# Processor.net
KiCad netlist of a schematic drawn in EAGLE
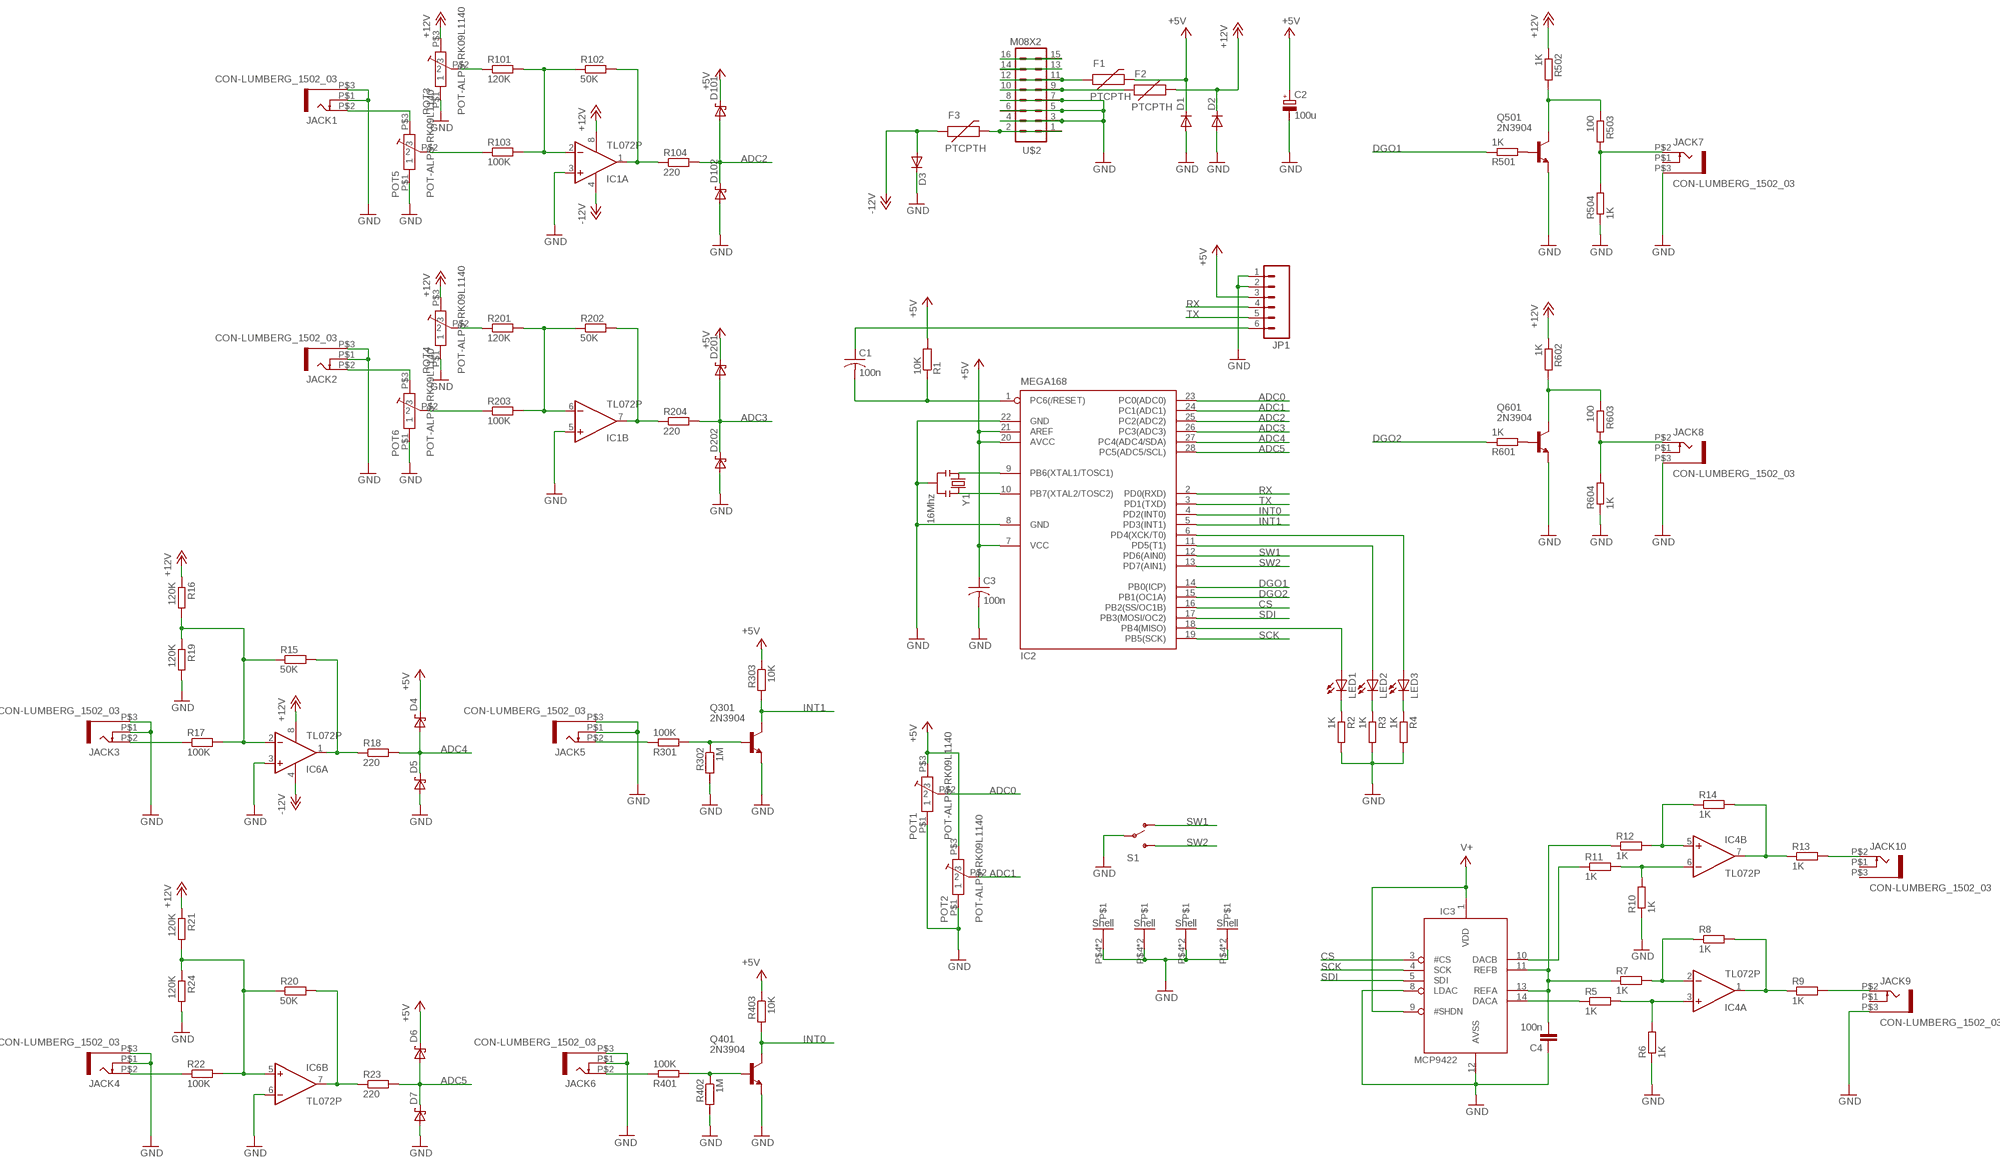
[diagram p0: schematic, sheet 1]

(export (version "E")
  (design (tool "Eeschema 10.0.6"))
  (components
    (comp (ref "C1")
      (value "100n")
      (footprint "eagle-import:C050-024X044")
      (libsource (lib "eagle-import") (part "C-US050-024X044"))
    )
    (comp (ref "C2")
      (value "100u")
      (footprint "eagle-import:E5-6")
      (libsource (lib "eagle-import") (part "CPOL-EUE5-6"))
    )
    (comp (ref "C3")
      (value "100n")
      (footprint "eagle-import:C050-024X044")
      (libsource (lib "eagle-import") (part "C-US050-024X044"))
    )
    (comp (ref "C4")
      (value "100n")
      (footprint "eagle-import:C050-030X075")
      (libsource (lib "eagle-import") (part "C-EU050-030X075"))
    )
    (comp (ref "D1")
      (value "DIODEPTH")
      (footprint "eagle-import:DIODE-1N4001")
      (libsource (lib "eagle-import") (part "DIODEPTH"))
    )
    (comp (ref "D2")
      (value "DIODEPTH")
      (footprint "eagle-import:DIODE-1N4001")
      (libsource (lib "eagle-import") (part "DIODEPTH"))
    )
    (comp (ref "D3")
      (value "DIODEPTH")
      (footprint "eagle-import:DIODE-1N4001")
      (libsource (lib "eagle-import") (part "DIODEPTH"))
    )
    (comp (ref "D4")
      (value "DS_E2L")
      (footprint "eagle-import:E2LINE")
      (libsource (lib "eagle-import") (part "DS_E2L"))
    )
    (comp (ref "D5")
      (value "DS_E2L")
      (footprint "eagle-import:E2LINE")
      (fields (field (name "OC_FARNELL") "unknown") (field (name "OC_NEWARK") "unknown"))
      (libsource (lib "eagle-import") (part "DS_E2L"))
    )
    (comp (ref "D6")
      (value "DS_E2L")
      (footprint "eagle-import:E2LINE")
      (libsource (lib "eagle-import") (part "DS_E2L"))
    )
    (comp (ref "D7")
      (value "DS_E2L")
      (footprint "eagle-import:E2LINE")
      (fields (field (name "OC_FARNELL") "unknown") (field (name "OC_NEWARK") "unknown"))
      (libsource (lib "eagle-import") (part "DS_E2L"))
    )
    (comp (ref "D101")
      (value "DS_E2L")
      (footprint "eagle-import:E2LINE")
      (libsource (lib "eagle-import") (part "DS_E2L"))
    )
    (comp (ref "D102")
      (value "DS_E2L")
      (footprint "eagle-import:E2LINE")
      (fields (field (name "OC_FARNELL") "unknown") (field (name "OC_NEWARK") "unknown"))
      (libsource (lib "eagle-import") (part "DS_E2L"))
    )
    (comp (ref "D201")
      (value "DS_E2L")
      (footprint "eagle-import:E2LINE")
      (libsource (lib "eagle-import") (part "DS_E2L"))
    )
    (comp (ref "D202")
      (value "DS_E2L")
      (footprint "eagle-import:E2LINE")
      (fields (field (name "OC_FARNELL") "unknown") (field (name "OC_NEWARK") "unknown"))
      (libsource (lib "eagle-import") (part "DS_E2L"))
    )
    (comp (ref "F1")
      (value "PTCPTH")
      (footprint "eagle-import:PTC")
      (libsource (lib "eagle-import") (part "PTCPTH"))
    )
    (comp (ref "F2")
      (value "PTCPTH")
      (footprint "eagle-import:PTC")
      (libsource (lib "eagle-import") (part "PTCPTH"))
    )
    (comp (ref "F3")
      (value "PTCPTH")
      (footprint "eagle-import:PTC")
      (libsource (lib "eagle-import") (part "PTCPTH"))
    )
    (comp (ref "IC1")
      (value "TL072P")
      (footprint "eagle-import:DIL08")
      (libsource (lib "eagle-import") (part "TL072P"))
    )
    (comp (ref "IC2")
      (value "MEGA168")
      (footprint "eagle-import:DIL28-3")
      (libsource (lib "eagle-import") (part "MEGA8-P"))
    )
    (comp (ref "IC3")
      (value "MCP9422")
      (footprint "eagle-import:DIL14")
      (libsource (lib "eagle-import") (part "MCP9422"))
    )
    (comp (ref "IC4")
      (value "TL072P")
      (footprint "eagle-import:DIL08")
      (libsource (lib "eagle-import") (part "TL072P"))
    )
    (comp (ref "IC6")
      (value "TL072P")
      (footprint "eagle-import:DIL08")
      (libsource (lib "eagle-import") (part "TL072P"))
    )
    (comp (ref "JACK1")
      (value "CON-LUMBERG_1502_03")
      (footprint "eagle-import:CON-LUMBERG_1502_03")
      (libsource (lib "eagle-import") (part "CON-LUMBERG_1502_03"))
    )
    (comp (ref "JACK2")
      (value "CON-LUMBERG_1502_03")
      (footprint "eagle-import:CON-LUMBERG_1502_03")
      (libsource (lib "eagle-import") (part "CON-LUMBERG_1502_03"))
    )
    (comp (ref "JACK3")
      (value "CON-LUMBERG_1502_03")
      (footprint "eagle-import:CON-LUMBERG_1502_03")
      (libsource (lib "eagle-import") (part "CON-LUMBERG_1502_03"))
    )
    (comp (ref "JACK4")
      (value "CON-LUMBERG_1502_03")
      (footprint "eagle-import:CON-LUMBERG_1502_03")
      (libsource (lib "eagle-import") (part "CON-LUMBERG_1502_03"))
    )
    (comp (ref "JACK5")
      (value "CON-LUMBERG_1502_03")
      (footprint "eagle-import:CON-LUMBERG_1502_03")
      (libsource (lib "eagle-import") (part "CON-LUMBERG_1502_03"))
    )
    (comp (ref "JACK6")
      (value "CON-LUMBERG_1502_03")
      (footprint "eagle-import:CON-LUMBERG_1502_03")
      (libsource (lib "eagle-import") (part "CON-LUMBERG_1502_03"))
    )
    (comp (ref "JACK7")
      (value "CON-LUMBERG_1502_03")
      (footprint "eagle-import:CON-LUMBERG_1502_03")
      (libsource (lib "eagle-import") (part "CON-LUMBERG_1502_03"))
    )
    (comp (ref "JACK8")
      (value "CON-LUMBERG_1502_03")
      (footprint "eagle-import:CON-LUMBERG_1502_03")
      (libsource (lib "eagle-import") (part "CON-LUMBERG_1502_03"))
    )
    (comp (ref "JACK9")
      (value "CON-LUMBERG_1502_03")
      (footprint "eagle-import:CON-LUMBERG_1502_03")
      (libsource (lib "eagle-import") (part "CON-LUMBERG_1502_03"))
    )
    (comp (ref "JACK10")
      (value "CON-LUMBERG_1502_03")
      (footprint "eagle-import:CON-LUMBERG_1502_03")
      (libsource (lib "eagle-import") (part "CON-LUMBERG_1502_03"))
    )
    (comp (ref "JP1")
      (value "M06SIP")
      (footprint "eagle-import:1X06")
      (libsource (lib "eagle-import") (part "M06SIP"))
    )
    (comp (ref "LED1")
      (value "LED3MM")
      (footprint "eagle-import:LED3MM")
      (libsource (lib "eagle-import") (part "LED3MM"))
    )
    (comp (ref "LED2")
      (value "LED3MM")
      (footprint "eagle-import:LED3MM")
      (libsource (lib "eagle-import") (part "LED3MM"))
    )
    (comp (ref "LED3")
      (value "LED3MM")
      (footprint "eagle-import:LED3MM")
      (libsource (lib "eagle-import") (part "LED3MM"))
    )
    (comp (ref "POT1")
      (value "POT-ALPS-RK09L1140")
      (footprint "eagle-import:POT-ALPS-RK09L1140")
      (libsource (lib "eagle-import") (part "POT-ALPS-RK09L1140"))
    )
    (comp (ref "POT2")
      (value "POT-ALPS-RK09L1140")
      (footprint "eagle-import:POT-ALPS-RK09L1140")
      (libsource (lib "eagle-import") (part "POT-ALPS-RK09L1140"))
    )
    (comp (ref "POT3")
      (value "POT-ALPS-RK09L1140")
      (footprint "eagle-import:POT-ALPS-RK09L1140")
      (libsource (lib "eagle-import") (part "POT-ALPS-RK09L1140"))
    )
    (comp (ref "POT4")
      (value "POT-ALPS-RK09L1140")
      (footprint "eagle-import:POT-ALPS-RK09L1140")
      (libsource (lib "eagle-import") (part "POT-ALPS-RK09L1140"))
    )
    (comp (ref "POT5")
      (value "POT-ALPS-RK09L1140")
      (footprint "eagle-import:POT-ALPS-RK09L1140")
      (libsource (lib "eagle-import") (part "POT-ALPS-RK09L1140"))
    )
    (comp (ref "POT6")
      (value "POT-ALPS-RK09L1140")
      (footprint "eagle-import:POT-ALPS-RK09L1140")
      (libsource (lib "eagle-import") (part "POT-ALPS-RK09L1140"))
    )
    (comp (ref "Q301")
      (value "2N3904")
      (footprint "eagle-import:TO92")
      (libsource (lib "eagle-import") (part "2N3904"))
    )
    (comp (ref "Q401")
      (value "2N3904")
      (footprint "eagle-import:TO92")
      (libsource (lib "eagle-import") (part "2N3904"))
    )
    (comp (ref "Q501")
      (value "2N3904")
      (footprint "eagle-import:TO92")
      (libsource (lib "eagle-import") (part "2N3904"))
    )
    (comp (ref "Q601")
      (value "2N3904")
      (footprint "eagle-import:TO92")
      (libsource (lib "eagle-import") (part "2N3904"))
    )
    (comp (ref "R1")
      (value "10K")
      (footprint "eagle-import:0204_7")
      (libsource (lib "eagle-import") (part "R-EU_0204/7"))
    )
    (comp (ref "R2")
      (value "1K")
      (footprint "eagle-import:0204_7")
      (libsource (lib "eagle-import") (part "R-EU_0204/7"))
    )
    (comp (ref "R3")
      (value "1K")
      (footprint "eagle-import:0204_7")
      (libsource (lib "eagle-import") (part "R-EU_0204/7"))
    )
    (comp (ref "R4")
      (value "1K")
      (footprint "eagle-import:0204_7")
      (libsource (lib "eagle-import") (part "R-EU_0204/7"))
    )
    (comp (ref "R5")
      (value "1K")
      (footprint "eagle-import:0204_7")
      (libsource (lib "eagle-import") (part "R-EU_0204/7"))
    )
    (comp (ref "R6")
      (value "1K")
      (footprint "eagle-import:0204_7")
      (libsource (lib "eagle-import") (part "R-EU_0204/7"))
    )
    (comp (ref "R7")
      (value "1K")
      (footprint "eagle-import:0204_7")
      (libsource (lib "eagle-import") (part "R-EU_0204/7"))
    )
    (comp (ref "R8")
      (value "1K")
      (footprint "eagle-import:0204_7")
      (libsource (lib "eagle-import") (part "R-EU_0204/7"))
    )
    (comp (ref "R9")
      (value "1K")
      (footprint "eagle-import:0204_7")
      (libsource (lib "eagle-import") (part "R-EU_0204/7"))
    )
    (comp (ref "R10")
      (value "1K")
      (footprint "eagle-import:0204_7")
      (libsource (lib "eagle-import") (part "R-EU_0204/7"))
    )
    (comp (ref "R11")
      (value "1K")
      (footprint "eagle-import:0204_7")
      (libsource (lib "eagle-import") (part "R-EU_0204/7"))
    )
    (comp (ref "R12")
      (value "1K")
      (footprint "eagle-import:0204_7")
      (libsource (lib "eagle-import") (part "R-EU_0204/7"))
    )
    (comp (ref "R13")
      (value "1K")
      (footprint "eagle-import:0204_7")
      (libsource (lib "eagle-import") (part "R-EU_0204/7"))
    )
    (comp (ref "R14")
      (value "1K")
      (footprint "eagle-import:0204_7")
      (libsource (lib "eagle-import") (part "R-EU_0204/7"))
    )
    (comp (ref "R15")
      (value "50K")
      (footprint "eagle-import:0204_7")
      (libsource (lib "eagle-import") (part "resistor_R-EU_0204/7"))
    )
    (comp (ref "R16")
      (value "120K")
      (footprint "eagle-import:0204_7")
      (libsource (lib "eagle-import") (part "resistor_R-EU_0204/7"))
    )
    (comp (ref "R17")
      (value "100K")
      (footprint "eagle-import:0204_7")
      (libsource (lib "eagle-import") (part "resistor_R-EU_0204/7"))
    )
    (comp (ref "R18")
      (value "220")
      (footprint "eagle-import:0204_7")
      (libsource (lib "eagle-import") (part "resistor_R-EU_0204/7"))
    )
    (comp (ref "R19")
      (value "120K")
      (footprint "eagle-import:0204_7")
      (libsource (lib "eagle-import") (part "resistor_R-EU_0204/7"))
    )
    (comp (ref "R20")
      (value "50K")
      (footprint "eagle-import:0204_7")
      (libsource (lib "eagle-import") (part "resistor_R-EU_0204/7"))
    )
    (comp (ref "R21")
      (value "120K")
      (footprint "eagle-import:0204_7")
      (libsource (lib "eagle-import") (part "resistor_R-EU_0204/7"))
    )
    (comp (ref "R22")
      (value "100K")
      (footprint "eagle-import:0204_7")
      (libsource (lib "eagle-import") (part "resistor_R-EU_0204/7"))
    )
    (comp (ref "R23")
      (value "220")
      (footprint "eagle-import:0204_7")
      (libsource (lib "eagle-import") (part "resistor_R-EU_0204/7"))
    )
    (comp (ref "R24")
      (value "120K")
      (footprint "eagle-import:0204_7")
      (libsource (lib "eagle-import") (part "resistor_R-EU_0204/7"))
    )
    (comp (ref "R101")
      (value "120K")
      (footprint "eagle-import:0204_7")
      (libsource (lib "eagle-import") (part "resistor_R-EU_0204/7"))
    )
    (comp (ref "R102")
      (value "50K")
      (footprint "eagle-import:0204_7")
      (libsource (lib "eagle-import") (part "resistor_R-EU_0204/7"))
    )
    (comp (ref "R103")
      (value "100K")
      (footprint "eagle-import:0204_7")
      (libsource (lib "eagle-import") (part "resistor_R-EU_0204/7"))
    )
    (comp (ref "R104")
      (value "220")
      (footprint "eagle-import:0204_7")
      (libsource (lib "eagle-import") (part "resistor_R-EU_0204/7"))
    )
    (comp (ref "R201")
      (value "120K")
      (footprint "eagle-import:0204_7")
      (libsource (lib "eagle-import") (part "resistor_R-EU_0204/7"))
    )
    (comp (ref "R202")
      (value "50K")
      (footprint "eagle-import:0204_7")
      (libsource (lib "eagle-import") (part "resistor_R-EU_0204/7"))
    )
    (comp (ref "R203")
      (value "100K")
      (footprint "eagle-import:0204_7")
      (libsource (lib "eagle-import") (part "resistor_R-EU_0204/7"))
    )
    (comp (ref "R204")
      (value "220")
      (footprint "eagle-import:0204_7")
      (libsource (lib "eagle-import") (part "resistor_R-EU_0204/7"))
    )
    (comp (ref "R301")
      (value "100K")
      (footprint "eagle-import:0204_7")
      (libsource (lib "eagle-import") (part "R-EU_0204/7"))
    )
    (comp (ref "R302")
      (value "1M")
      (footprint "eagle-import:0204_7")
      (libsource (lib "eagle-import") (part "R-EU_0204/7"))
    )
    (comp (ref "R303")
      (value "10K")
      (footprint "eagle-import:0204_7")
      (libsource (lib "eagle-import") (part "R-EU_0204/7"))
    )
    (comp (ref "R401")
      (value "100K")
      (footprint "eagle-import:0204_7")
      (libsource (lib "eagle-import") (part "R-EU_0204/7"))
    )
    (comp (ref "R402")
      (value "1M")
      (footprint "eagle-import:0204_7")
      (libsource (lib "eagle-import") (part "R-EU_0204/7"))
    )
    (comp (ref "R403")
      (value "10K")
      (footprint "eagle-import:0204_7")
      (libsource (lib "eagle-import") (part "R-EU_0204/7"))
    )
    (comp (ref "R501")
      (value "1K")
      (footprint "eagle-import:0204_7")
      (libsource (lib "eagle-import") (part "R-EU_0204/7"))
    )
    (comp (ref "R502")
      (value "1K")
      (footprint "eagle-import:0204_7")
      (libsource (lib "eagle-import") (part "R-EU_0204/7"))
    )
    (comp (ref "R503")
      (value "100")
      (footprint "eagle-import:0204_7")
      (libsource (lib "eagle-import") (part "R-EU_0204/7"))
    )
    (comp (ref "R504")
      (value "1K")
      (footprint "eagle-import:0204_7")
      (libsource (lib "eagle-import") (part "R-EU_0204/7"))
    )
    (comp (ref "R601")
      (value "1K")
      (footprint "eagle-import:0204_7")
      (libsource (lib "eagle-import") (part "R-EU_0204/7"))
    )
    (comp (ref "R602")
      (value "1K")
      (footprint "eagle-import:0204_7")
      (libsource (lib "eagle-import") (part "R-EU_0204/7"))
    )
    (comp (ref "R603")
      (value "100")
      (footprint "eagle-import:0204_7")
      (libsource (lib "eagle-import") (part "R-EU_0204/7"))
    )
    (comp (ref "R604")
      (value "1K")
      (footprint "eagle-import:0204_7")
      (libsource (lib "eagle-import") (part "R-EU_0204/7"))
    )
    (comp (ref "S1")
      (value "SWITCH-SPST")
      (footprint "eagle-import:SWITCH-SPDT-SALECOM-T8014")
      (libsource (lib "eagle-import") (part "SWITCH-SPST"))
    )
    (comp (ref "U$2")
      (value "M08X2")
      (footprint "eagle-import:2X8")
      (libsource (lib "eagle-import") (part "M08X2"))
    )
    (comp (ref "Y1")
      (value "16Mhz")
      (footprint "eagle-import:RESONATOR-PTH")
      (libsource (lib "eagle-import") (part "RESONATORPTH"))
    )
  )
  (nets
    (net (code "1") (name "+5V") (class "Default")
      (node (ref "C2") (pin "+") (pinfunction "+_+") (pintype "passive"))
      (node (ref "C3") (pin "1") (pinfunction "1_1") (pintype "passive"))
      (node (ref "D1") (pin "C") (pinfunction "C_C") (pintype "passive"))
      (node (ref "D101") (pin "1") (pinfunction "K_1") (pintype "passive"))
      (node (ref "D201") (pin "1") (pinfunction "K_1") (pintype "passive"))
      (node (ref "D4") (pin "1") (pinfunction "K_1") (pintype "passive"))
      (node (ref "D6") (pin "1") (pinfunction "K_1") (pintype "passive"))
      (node (ref "F1") (pin "P$2") (pinfunction "2_P$2") (pintype "bidirectional"))
      (node (ref "IC2") (pin "20") (pinfunction "AVCC_20") (pintype "power_in"))
      (node (ref "IC2") (pin "21") (pinfunction "AREF_21") (pintype "passive"))
      (node (ref "IC2") (pin "7") (pinfunction "VCC_7") (pintype "power_in"))
      (node (ref "JP1") (pin "3") (pinfunction "3_3") (pintype "passive"))
      (node (ref "POT1") (pin "P$3") (pinfunction "3_P$3") (pintype "bidirectional"))
      (node (ref "POT2") (pin "P$3") (pinfunction "3_P$3") (pintype "bidirectional"))
      (node (ref "R1") (pin "2") (pinfunction "2_2") (pintype "passive"))
      (node (ref "R303") (pin "1") (pinfunction "1_1") (pintype "passive"))
      (node (ref "R403") (pin "1") (pinfunction "1_1") (pintype "passive"))
    )
    (net (code "2") (name "+12V") (class "Default")
      (node (ref "D2") (pin "C") (pinfunction "C_C") (pintype "passive"))
      (node (ref "F2") (pin "P$2") (pinfunction "2_P$2") (pintype "bidirectional"))
      (node (ref "IC1") (pin "8") (pinfunction "V+_8") (pintype "power_in"))
      (node (ref "IC6") (pin "8") (pinfunction "V+_8") (pintype "power_in"))
      (node (ref "POT3") (pin "P$3") (pinfunction "3_P$3") (pintype "bidirectional"))
      (node (ref "POT4") (pin "P$3") (pinfunction "3_P$3") (pintype "bidirectional"))
      (node (ref "R16") (pin "1") (pinfunction "1_1") (pintype "passive"))
      (node (ref "R21") (pin "1") (pinfunction "1_1") (pintype "passive"))
      (node (ref "R502") (pin "1") (pinfunction "1_1") (pintype "passive"))
      (node (ref "R602") (pin "1") (pinfunction "1_1") (pintype "passive"))
    )
    (net (code "3") (name "-12V") (class "Default")
      (node (ref "D3") (pin "A") (pinfunction "A_A") (pintype "passive"))
      (node (ref "F3") (pin "P$1") (pinfunction "1_P$1") (pintype "bidirectional"))
      (node (ref "IC1") (pin "4") (pinfunction "V-_4") (pintype "power_in"))
      (node (ref "IC6") (pin "4") (pinfunction "V-_4") (pintype "power_in"))
    )
    (net (code "4") (name "/ADC0") (class "Default")
      (node (ref "IC2") (pin "23") (pinfunction "PC0(ADC0)_23") (pintype "bidirectional"))
      (node (ref "POT1") (pin "P$2") (pinfunction "2_P$2") (pintype "bidirectional"))
    )
    (net (code "5") (name "/ADC1") (class "Default")
      (node (ref "IC2") (pin "24") (pinfunction "PC1(ADC1)_24") (pintype "bidirectional"))
      (node (ref "POT2") (pin "P$2") (pinfunction "2_P$2") (pintype "bidirectional"))
    )
    (net (code "6") (name "/ADC2") (class "Default")
      (node (ref "D101") (pin "2") (pinfunction "A_2") (pintype "passive"))
      (node (ref "D102") (pin "1") (pinfunction "K_1") (pintype "passive"))
      (node (ref "IC2") (pin "25") (pinfunction "PC2(ADC2)_25") (pintype "bidirectional"))
      (node (ref "R104") (pin "2") (pinfunction "2_2") (pintype "passive"))
    )
    (net (code "7") (name "/ADC3") (class "Default")
      (node (ref "D201") (pin "2") (pinfunction "A_2") (pintype "passive"))
      (node (ref "D202") (pin "1") (pinfunction "K_1") (pintype "passive"))
      (node (ref "IC2") (pin "26") (pinfunction "PC3(ADC3)_26") (pintype "bidirectional"))
      (node (ref "R204") (pin "2") (pinfunction "2_2") (pintype "passive"))
    )
    (net (code "8") (name "/ADC4") (class "Default")
      (node (ref "D4") (pin "2") (pinfunction "A_2") (pintype "passive"))
      (node (ref "D5") (pin "1") (pinfunction "K_1") (pintype "passive"))
      (node (ref "IC2") (pin "27") (pinfunction "PC4(ADC4/SDA)_27") (pintype "bidirectional"))
      (node (ref "R18") (pin "2") (pinfunction "2_2") (pintype "passive"))
    )
    (net (code "9") (name "/ADC5") (class "Default")
      (node (ref "D6") (pin "2") (pinfunction "A_2") (pintype "passive"))
      (node (ref "D7") (pin "1") (pinfunction "K_1") (pintype "passive"))
      (node (ref "IC2") (pin "28") (pinfunction "PC5(ADC5/SCL)_28") (pintype "bidirectional"))
      (node (ref "R23") (pin "2") (pinfunction "2_2") (pintype "passive"))
    )
    (net (code "10") (name "/CS") (class "Default")
      (node (ref "IC2") (pin "16") (pinfunction "PB2(SS/OC1B)_16") (pintype "bidirectional"))
      (node (ref "IC3") (pin "3") (pinfunction "#CS_3") (pintype "input"))
    )
    (net (code "11") (name "/DGO1") (class "Default")
      (node (ref "IC2") (pin "14") (pinfunction "PB0(ICP)_14") (pintype "bidirectional"))
      (node (ref "R501") (pin "1") (pinfunction "1_1") (pintype "passive"))
    )
    (net (code "12") (name "/DGO2") (class "Default")
      (node (ref "IC2") (pin "15") (pinfunction "PB1(OC1A)_15") (pintype "bidirectional"))
      (node (ref "R601") (pin "1") (pinfunction "1_1") (pintype "passive"))
    )
    (net (code "13") (name "/INT0") (class "Default")
      (node (ref "IC2") (pin "4") (pinfunction "PD2(INT0)_4") (pintype "bidirectional"))
      (node (ref "Q401") (pin "1") (pinfunction "C_1") (pintype "passive"))
      (node (ref "R403") (pin "2") (pinfunction "2_2") (pintype "passive"))
    )
    (net (code "14") (name "/INT1") (class "Default")
      (node (ref "IC2") (pin "5") (pinfunction "PD3(INT1)_5") (pintype "bidirectional"))
      (node (ref "Q301") (pin "1") (pinfunction "C_1") (pintype "passive"))
      (node (ref "R303") (pin "2") (pinfunction "2_2") (pintype "passive"))
    )
    (net (code "15") (name "/RX") (class "Default")
      (node (ref "IC2") (pin "2") (pinfunction "PD0(RXD)_2") (pintype "bidirectional"))
      (node (ref "JP1") (pin "4") (pinfunction "4_4") (pintype "passive"))
    )
    (net (code "16") (name "/SCK") (class "Default")
      (node (ref "IC2") (pin "19") (pinfunction "PB5(SCK)_19") (pintype "bidirectional"))
      (node (ref "IC3") (pin "4") (pinfunction "SCK_4") (pintype "input"))
    )
    (net (code "17") (name "/SDI") (class "Default")
      (node (ref "IC2") (pin "17") (pinfunction "PB3(MOSI/OC2)_17") (pintype "bidirectional"))
      (node (ref "IC3") (pin "5") (pinfunction "SDI_5") (pintype "input"))
    )
    (net (code "18") (name "/SW1") (class "Default")
      (node (ref "IC2") (pin "12") (pinfunction "PD6(AIN0)_12") (pintype "bidirectional"))
      (node (ref "S1") (pin "1") (pinfunction "O_1") (pintype "passive"))
    )
    (net (code "19") (name "/SW2") (class "Default")
      (node (ref "IC2") (pin "13") (pinfunction "PD7(AIN1)_13") (pintype "bidirectional"))
      (node (ref "S1") (pin "3") (pinfunction "S_3") (pintype "passive"))
    )
    (net (code "20") (name "/TX") (class "Default")
      (node (ref "IC2") (pin "3") (pinfunction "PD1(TXD)_3") (pintype "bidirectional"))
      (node (ref "JP1") (pin "5") (pinfunction "5_5") (pintype "passive"))
    )
    (net (code "21") (name "GND") (class "Default")
      (node (ref "C2") (pin "-") (pinfunction "-_-") (pintype "passive"))
      (node (ref "C3") (pin "2") (pinfunction "2_2") (pintype "passive"))
      (node (ref "C4") (pin "1") (pinfunction "1_1") (pintype "passive"))
      (node (ref "D1") (pin "A") (pinfunction "A_A") (pintype "passive"))
      (node (ref "D102") (pin "2") (pinfunction "A_2") (pintype "passive"))
      (node (ref "D2") (pin "A") (pinfunction "A_A") (pintype "passive"))
      (node (ref "D202") (pin "2") (pinfunction "A_2") (pintype "passive"))
      (node (ref "D3") (pin "C") (pinfunction "C_C") (pintype "passive"))
      (node (ref "D5") (pin "2") (pinfunction "A_2") (pintype "passive"))
      (node (ref "D7") (pin "2") (pinfunction "A_2") (pintype "passive"))
      (node (ref "IC1") (pin "3") (pinfunction "+IN_3") (pintype "input"))
      (node (ref "IC1") (pin "5") (pinfunction "+IN_5") (pintype "input"))
      (node (ref "IC2") (pin "22") (pinfunction "GND_22") (pintype "power_in"))
      (node (ref "IC2") (pin "8") (pinfunction "GND_8") (pintype "power_in"))
      (node (ref "IC3") (pin "12") (pinfunction "AVSS_12") (pintype "power_in"))
      (node (ref "IC3") (pin "8") (pinfunction "LDAC_8") (pintype "input"))
      (node (ref "IC6") (pin "3") (pinfunction "+IN_3") (pintype "input"))
      (node (ref "IC6") (pin "6") (pinfunction "-IN_6") (pintype "input"))
      (node (ref "JACK1") (pin "P$1") (pinfunction "4_P$1") (pintype "passive"))
      (node (ref "JACK1") (pin "P$3") (pinfunction "5_P$3") (pintype "passive"))
      (node (ref "JACK2") (pin "P$1") (pinfunction "4_P$1") (pintype "passive"))
      (node (ref "JACK2") (pin "P$3") (pinfunction "5_P$3") (pintype "passive"))
      (node (ref "JACK3") (pin "P$1") (pinfunction "4_P$1") (pintype "passive"))
      (node (ref "JACK3") (pin "P$3") (pinfunction "5_P$3") (pintype "passive"))
      (node (ref "JACK4") (pin "P$1") (pinfunction "4_P$1") (pintype "passive"))
      (node (ref "JACK4") (pin "P$3") (pinfunction "5_P$3") (pintype "passive"))
      (node (ref "JACK5") (pin "P$1") (pinfunction "4_P$1") (pintype "passive"))
      (node (ref "JACK5") (pin "P$3") (pinfunction "5_P$3") (pintype "passive"))
      (node (ref "JACK6") (pin "P$1") (pinfunction "4_P$1") (pintype "passive"))
      (node (ref "JACK6") (pin "P$3") (pinfunction "5_P$3") (pintype "passive"))
      (node (ref "JACK7") (pin "P$3") (pinfunction "5_P$3") (pintype "passive"))
      (node (ref "JACK8") (pin "P$3") (pinfunction "5_P$3") (pintype "passive"))
      (node (ref "JACK9") (pin "P$3") (pinfunction "5_P$3") (pintype "passive"))
      (node (ref "JP1") (pin "1") (pinfunction "1_1") (pintype "passive"))
      (node (ref "JP1") (pin "2") (pinfunction "2_2") (pintype "passive"))
      (node (ref "POT1") (pin "P$1") (pinfunction "1_P$1") (pintype "bidirectional"))
      (node (ref "POT2") (pin "P$1") (pinfunction "1_P$1") (pintype "bidirectional"))
      (node (ref "POT3") (pin "P$1") (pinfunction "1_P$1") (pintype "bidirectional"))
      (node (ref "POT3") (pin "P$4") (pinfunction "P$1_P$4") (pintype "bidirectional"))
      (node (ref "POT3") (pin "P$6") (pinfunction "P$1_P$6") (pintype "bidirectional"))
      (node (ref "POT4") (pin "P$1") (pinfunction "1_P$1") (pintype "bidirectional"))
      (node (ref "POT4") (pin "P$4") (pinfunction "P$1_P$4") (pintype "bidirectional"))
      (node (ref "POT4") (pin "P$6") (pinfunction "P$1_P$6") (pintype "bidirectional"))
      (node (ref "POT5") (pin "P$1") (pinfunction "1_P$1") (pintype "bidirectional"))
      (node (ref "POT5") (pin "P$4") (pinfunction "P$1_P$4") (pintype "bidirectional"))
      (node (ref "POT5") (pin "P$6") (pinfunction "P$1_P$6") (pintype "bidirectional"))
      (node (ref "POT6") (pin "P$1") (pinfunction "1_P$1") (pintype "bidirectional"))
      (node (ref "POT6") (pin "P$4") (pinfunction "P$1_P$4") (pintype "bidirectional"))
      (node (ref "POT6") (pin "P$6") (pinfunction "P$1_P$6") (pintype "bidirectional"))
      (node (ref "Q301") (pin "3") (pinfunction "E_3") (pintype "passive"))
      (node (ref "Q401") (pin "3") (pinfunction "E_3") (pintype "passive"))
      (node (ref "Q501") (pin "3") (pinfunction "E_3") (pintype "passive"))
      (node (ref "Q601") (pin "3") (pinfunction "E_3") (pintype "passive"))
      (node (ref "R10") (pin "1") (pinfunction "1_1") (pintype "passive"))
      (node (ref "R19") (pin "2") (pinfunction "2_2") (pintype "passive"))
      (node (ref "R2") (pin "2") (pinfunction "2_2") (pintype "passive"))
      (node (ref "R24") (pin "2") (pinfunction "2_2") (pintype "passive"))
      (node (ref "R3") (pin "2") (pinfunction "2_2") (pintype "passive"))
      (node (ref "R302") (pin "2") (pinfunction "2_2") (pintype "passive"))
      (node (ref "R4") (pin "2") (pinfunction "2_2") (pintype "passive"))
      (node (ref "R402") (pin "2") (pinfunction "2_2") (pintype "passive"))
      (node (ref "R504") (pin "1") (pinfunction "1_1") (pintype "passive"))
      (node (ref "R6") (pin "1") (pinfunction "1_1") (pintype "passive"))
      (node (ref "R604") (pin "1") (pinfunction "1_1") (pintype "passive"))
      (node (ref "S1") (pin "2") (pinfunction "P_2") (pintype "passive"))
      (node (ref "U$2") (pin "3") (pinfunction "3_3") (pintype "passive"))
      (node (ref "U$2") (pin "4") (pinfunction "4_4") (pintype "passive"))
      (node (ref "U$2") (pin "5") (pinfunction "5_5") (pintype "passive"))
      (node (ref "U$2") (pin "6") (pinfunction "6_6") (pintype "passive"))
      (node (ref "U$2") (pin "7") (pinfunction "7_7") (pintype "passive"))
      (node (ref "U$2") (pin "8") (pinfunction "8_8") (pintype "passive"))
      (node (ref "Y1") (pin "2") (pinfunction "2_2") (pintype "passive"))
    )
    (net (code "22") (name "Net-(C1-Pad1)") (class "Default")
      (node (ref "C1") (pin "1") (pinfunction "1_1") (pintype "passive"))
      (node (ref "JP1") (pin "6") (pinfunction "6_6") (pintype "passive"))
    )
    (net (code "23") (name "Net-(F1-1)") (class "Default")
      (node (ref "F1") (pin "P$1") (pinfunction "1_P$1") (pintype "bidirectional"))
      (node (ref "U$2") (pin "11") (pinfunction "11_11") (pintype "passive"))
      (node (ref "U$2") (pin "12") (pinfunction "12_12") (pintype "passive"))
    )
    (net (code "24") (name "Net-(F2-1)") (class "Default")
      (node (ref "F2") (pin "P$1") (pinfunction "1_P$1") (pintype "bidirectional"))
      (node (ref "U$2") (pin "10") (pinfunction "10_10") (pintype "passive"))
      (node (ref "U$2") (pin "9") (pinfunction "9_9") (pintype "passive"))
    )
    (net (code "25") (name "Net-(F3-2)") (class "Default")
      (node (ref "F3") (pin "P$2") (pinfunction "2_P$2") (pintype "bidirectional"))
      (node (ref "U$2") (pin "1") (pinfunction "1_1") (pintype "passive"))
      (node (ref "U$2") (pin "2") (pinfunction "2_2") (pintype "passive"))
    )
    (net (code "26") (name "Net-(IC1A--IN)") (class "Default")
      (node (ref "IC1") (pin "2") (pinfunction "-IN_2") (pintype "input"))
      (node (ref "R101") (pin "2") (pinfunction "2_2") (pintype "passive"))
      (node (ref "R102") (pin "1") (pinfunction "1_1") (pintype "passive"))
      (node (ref "R103") (pin "2") (pinfunction "2_2") (pintype "passive"))
    )
    (net (code "27") (name "Net-(IC1A-OUT)") (class "Default")
      (node (ref "IC1") (pin "1") (pinfunction "OUT_1") (pintype "output"))
      (node (ref "R102") (pin "2") (pinfunction "2_2") (pintype "passive"))
      (node (ref "R104") (pin "1") (pinfunction "1_1") (pintype "passive"))
    )
    (net (code "28") (name "Net-(IC1B--IN)") (class "Default")
      (node (ref "IC1") (pin "6") (pinfunction "-IN_6") (pintype "input"))
      (node (ref "R201") (pin "2") (pinfunction "2_2") (pintype "passive"))
      (node (ref "R202") (pin "1") (pinfunction "1_1") (pintype "passive"))
      (node (ref "R203") (pin "2") (pinfunction "2_2") (pintype "passive"))
    )
    (net (code "29") (name "Net-(IC1B-OUT)") (class "Default")
      (node (ref "IC1") (pin "7") (pinfunction "OUT_7") (pintype "output"))
      (node (ref "R202") (pin "2") (pinfunction "2_2") (pintype "passive"))
      (node (ref "R204") (pin "1") (pinfunction "1_1") (pintype "passive"))
    )
    (net (code "30") (name "Net-(IC2-PB4(MISO))") (class "Default")
      (node (ref "IC2") (pin "18") (pinfunction "PB4(MISO)_18") (pintype "bidirectional"))
      (node (ref "LED1") (pin "A") (pinfunction "A_A") (pintype "passive"))
    )
    (net (code "31") (name "Net-(IC2-PB6(XTAL1{slash}TOSC1))") (class "Default")
      (node (ref "IC2") (pin "9") (pinfunction "PB6(XTAL1/TOSC1)_9") (pintype "bidirectional"))
      (node (ref "Y1") (pin "1") (pinfunction "1_1") (pintype "passive"))
    )
    (net (code "32") (name "Net-(IC2-PB7(XTAL2{slash}TOSC2))") (class "Default")
      (node (ref "IC2") (pin "10") (pinfunction "PB7(XTAL2/TOSC2)_10") (pintype "bidirectional"))
      (node (ref "Y1") (pin "3") (pinfunction "3_3") (pintype "passive"))
    )
    (net (code "33") (name "Net-(IC2-PC6({slash}RESET))") (class "Default")
      (node (ref "C1") (pin "2") (pinfunction "2_2") (pintype "passive"))
      (node (ref "IC2") (pin "1") (pinfunction "PC6(/RESET)_1") (pintype "bidirectional"))
      (node (ref "R1") (pin "1") (pinfunction "1_1") (pintype "passive"))
    )
    (net (code "34") (name "Net-(IC2-PD4(XCK{slash}T0))") (class "Default")
      (node (ref "IC2") (pin "6") (pinfunction "PD4(XCK/T0)_6") (pintype "bidirectional"))
      (node (ref "LED3") (pin "A") (pinfunction "A_A") (pintype "passive"))
    )
    (net (code "35") (name "Net-(IC2-PD5(T1))") (class "Default")
      (node (ref "IC2") (pin "11") (pinfunction "PD5(T1)_11") (pintype "bidirectional"))
      (node (ref "LED2") (pin "A") (pinfunction "A_A") (pintype "passive"))
    )
    (net (code "36") (name "Net-(IC3-DACA)") (class "Default")
      (node (ref "IC3") (pin "14") (pinfunction "DACA_14") (pintype "output"))
      (node (ref "R5") (pin "1") (pinfunction "1_1") (pintype "passive"))
    )
    (net (code "37") (name "Net-(IC3-DACB)") (class "Default")
      (node (ref "IC3") (pin "10") (pinfunction "DACB_10") (pintype "output"))
      (node (ref "R11") (pin "1") (pinfunction "1_1") (pintype "passive"))
    )
    (net (code "38") (name "Net-(IC3-REFA)") (class "Default")
      (node (ref "C4") (pin "2") (pinfunction "2_2") (pintype "passive"))
      (node (ref "IC3") (pin "11") (pinfunction "REFB_11") (pintype "input"))
      (node (ref "IC3") (pin "13") (pinfunction "REFA_13") (pintype "input"))
      (node (ref "R12") (pin "1") (pinfunction "1_1") (pintype "passive"))
      (node (ref "R7") (pin "1") (pinfunction "1_1") (pintype "passive"))
    )
    (net (code "39") (name "Net-(IC4A-+IN)") (class "Default")
      (node (ref "IC4") (pin "3") (pinfunction "+IN_3") (pintype "input"))
      (node (ref "R5") (pin "2") (pinfunction "2_2") (pintype "passive"))
      (node (ref "R6") (pin "2") (pinfunction "2_2") (pintype "passive"))
    )
    (net (code "40") (name "Net-(IC4A--IN)") (class "Default")
      (node (ref "IC4") (pin "2") (pinfunction "-IN_2") (pintype "input"))
      (node (ref "R7") (pin "2") (pinfunction "2_2") (pintype "passive"))
      (node (ref "R8") (pin "1") (pinfunction "1_1") (pintype "passive"))
    )
    (net (code "41") (name "Net-(IC4A-OUT)") (class "Default")
      (node (ref "IC4") (pin "1") (pinfunction "OUT_1") (pintype "output"))
      (node (ref "R8") (pin "2") (pinfunction "2_2") (pintype "passive"))
      (node (ref "R9") (pin "1") (pinfunction "1_1") (pintype "passive"))
    )
    (net (code "42") (name "Net-(IC4B-+IN)") (class "Default")
      (node (ref "IC4") (pin "5") (pinfunction "+IN_5") (pintype "input"))
      (node (ref "R12") (pin "2") (pinfunction "2_2") (pintype "passive"))
      (node (ref "R14") (pin "1") (pinfunction "1_1") (pintype "passive"))
    )
    (net (code "43") (name "Net-(IC4B--IN)") (class "Default")
      (node (ref "IC4") (pin "6") (pinfunction "-IN_6") (pintype "input"))
      (node (ref "R10") (pin "2") (pinfunction "2_2") (pintype "passive"))
      (node (ref "R11") (pin "2") (pinfunction "2_2") (pintype "passive"))
    )
    (net (code "44") (name "Net-(IC4B-OUT)") (class "Default")
      (node (ref "IC4") (pin "7") (pinfunction "OUT_7") (pintype "output"))
      (node (ref "R13") (pin "1") (pinfunction "1_1") (pintype "passive"))
      (node (ref "R14") (pin "2") (pinfunction "2_2") (pintype "passive"))
    )
    (net (code "45") (name "Net-(IC6A--IN)") (class "Default")
      (node (ref "IC6") (pin "2") (pinfunction "-IN_2") (pintype "input"))
      (node (ref "R15") (pin "1") (pinfunction "1_1") (pintype "passive"))
      (node (ref "R16") (pin "2") (pinfunction "2_2") (pintype "passive"))
      (node (ref "R17") (pin "2") (pinfunction "2_2") (pintype "passive"))
      (node (ref "R19") (pin "1") (pinfunction "1_1") (pintype "passive"))
    )
    (net (code "46") (name "Net-(IC6A-OUT)") (class "Default")
      (node (ref "IC6") (pin "1") (pinfunction "OUT_1") (pintype "output"))
      (node (ref "R15") (pin "2") (pinfunction "2_2") (pintype "passive"))
      (node (ref "R18") (pin "1") (pinfunction "1_1") (pintype "passive"))
    )
    (net (code "47") (name "Net-(IC6B-+IN)") (class "Default")
      (node (ref "IC6") (pin "5") (pinfunction "+IN_5") (pintype "input"))
      (node (ref "R20") (pin "1") (pinfunction "1_1") (pintype "passive"))
      (node (ref "R21") (pin "2") (pinfunction "2_2") (pintype "passive"))
      (node (ref "R22") (pin "2") (pinfunction "2_2") (pintype "passive"))
      (node (ref "R24") (pin "1") (pinfunction "1_1") (pintype "passive"))
    )
    (net (code "48") (name "Net-(IC6B-OUT)") (class "Default")
      (node (ref "IC6") (pin "7") (pinfunction "OUT_7") (pintype "output"))
      (node (ref "R20") (pin "2") (pinfunction "2_2") (pintype "passive"))
      (node (ref "R23") (pin "1") (pinfunction "1_1") (pintype "passive"))
    )
    (net (code "49") (name "Net-(JACK1-3)") (class "Default")
      (node (ref "JACK1") (pin "P$2") (pinfunction "3_P$2") (pintype "passive"))
      (node (ref "POT5") (pin "P$3") (pinfunction "3_P$3") (pintype "bidirectional"))
    )
    (net (code "50") (name "Net-(JACK2-3)") (class "Default")
      (node (ref "JACK2") (pin "P$2") (pinfunction "3_P$2") (pintype "passive"))
      (node (ref "POT6") (pin "P$3") (pinfunction "3_P$3") (pintype "bidirectional"))
    )
    (net (code "51") (name "Net-(JACK3-3)") (class "Default")
      (node (ref "JACK3") (pin "P$2") (pinfunction "3_P$2") (pintype "passive"))
      (node (ref "R17") (pin "1") (pinfunction "1_1") (pintype "passive"))
    )
    (net (code "52") (name "Net-(JACK4-3)") (class "Default")
      (node (ref "JACK4") (pin "P$2") (pinfunction "3_P$2") (pintype "passive"))
      (node (ref "R22") (pin "1") (pinfunction "1_1") (pintype "passive"))
    )
    (net (code "53") (name "Net-(JACK5-3)") (class "Default")
      (node (ref "JACK5") (pin "P$2") (pinfunction "3_P$2") (pintype "passive"))
      (node (ref "R301") (pin "1") (pinfunction "1_1") (pintype "passive"))
    )
    (net (code "54") (name "Net-(JACK6-3)") (class "Default")
      (node (ref "JACK6") (pin "P$2") (pinfunction "3_P$2") (pintype "passive"))
      (node (ref "R401") (pin "1") (pinfunction "1_1") (pintype "passive"))
    )
    (net (code "55") (name "Net-(JACK7-3)") (class "Default")
      (node (ref "JACK7") (pin "P$2") (pinfunction "3_P$2") (pintype "passive"))
      (node (ref "R503") (pin "2") (pinfunction "2_2") (pintype "passive"))
      (node (ref "R504") (pin "2") (pinfunction "2_2") (pintype "passive"))
    )
    (net (code "56") (name "Net-(JACK8-3)") (class "Default")
      (node (ref "JACK8") (pin "P$2") (pinfunction "3_P$2") (pintype "passive"))
      (node (ref "R603") (pin "2") (pinfunction "2_2") (pintype "passive"))
      (node (ref "R604") (pin "2") (pinfunction "2_2") (pintype "passive"))
    )
    (net (code "57") (name "Net-(JACK9-3)") (class "Default")
      (node (ref "JACK9") (pin "P$2") (pinfunction "3_P$2") (pintype "passive"))
      (node (ref "R9") (pin "2") (pinfunction "2_2") (pintype "passive"))
    )
    (net (code "58") (name "Net-(JACK10-3)") (class "Default")
      (node (ref "JACK10") (pin "P$2") (pinfunction "3_P$2") (pintype "passive"))
      (node (ref "R13") (pin "2") (pinfunction "2_2") (pintype "passive"))
    )
    (net (code "59") (name "Net-(LED1-C)") (class "Default")
      (node (ref "LED1") (pin "K") (pinfunction "C_K") (pintype "passive"))
      (node (ref "R2") (pin "1") (pinfunction "1_1") (pintype "passive"))
    )
    (net (code "60") (name "Net-(LED2-C)") (class "Default")
      (node (ref "LED2") (pin "K") (pinfunction "C_K") (pintype "passive"))
      (node (ref "R3") (pin "1") (pinfunction "1_1") (pintype "passive"))
    )
    (net (code "61") (name "Net-(LED3-C)") (class "Default")
      (node (ref "LED3") (pin "K") (pinfunction "C_K") (pintype "passive"))
      (node (ref "R4") (pin "1") (pinfunction "1_1") (pintype "passive"))
    )
    (net (code "62") (name "Net-(POT3A-2)") (class "Default")
      (node (ref "POT3") (pin "P$2") (pinfunction "2_P$2") (pintype "bidirectional"))
      (node (ref "R101") (pin "1") (pinfunction "1_1") (pintype "passive"))
    )
    (net (code "63") (name "Net-(POT4A-2)") (class "Default")
      (node (ref "POT4") (pin "P$2") (pinfunction "2_P$2") (pintype "bidirectional"))
      (node (ref "R201") (pin "1") (pinfunction "1_1") (pintype "passive"))
    )
    (net (code "64") (name "Net-(POT5A-2)") (class "Default")
      (node (ref "POT5") (pin "P$2") (pinfunction "2_P$2") (pintype "bidirectional"))
      (node (ref "R103") (pin "1") (pinfunction "1_1") (pintype "passive"))
    )
    (net (code "65") (name "Net-(POT6A-2)") (class "Default")
      (node (ref "POT6") (pin "P$2") (pinfunction "2_P$2") (pintype "bidirectional"))
      (node (ref "R203") (pin "1") (pinfunction "1_1") (pintype "passive"))
    )
    (net (code "66") (name "Net-(Q301-B)") (class "Default")
      (node (ref "Q301") (pin "2") (pinfunction "B_2") (pintype "passive"))
      (node (ref "R301") (pin "2") (pinfunction "2_2") (pintype "passive"))
      (node (ref "R302") (pin "1") (pinfunction "1_1") (pintype "passive"))
    )
    (net (code "67") (name "Net-(Q401-B)") (class "Default")
      (node (ref "Q401") (pin "2") (pinfunction "B_2") (pintype "passive"))
      (node (ref "R401") (pin "2") (pinfunction "2_2") (pintype "passive"))
      (node (ref "R402") (pin "1") (pinfunction "1_1") (pintype "passive"))
    )
    (net (code "68") (name "Net-(Q501-B)") (class "Default")
      (node (ref "Q501") (pin "2") (pinfunction "B_2") (pintype "passive"))
      (node (ref "R501") (pin "2") (pinfunction "2_2") (pintype "passive"))
    )
    (net (code "69") (name "Net-(Q501-C)") (class "Default")
      (node (ref "Q501") (pin "1") (pinfunction "C_1") (pintype "passive"))
      (node (ref "R502") (pin "2") (pinfunction "2_2") (pintype "passive"))
      (node (ref "R503") (pin "1") (pinfunction "1_1") (pintype "passive"))
    )
    (net (code "70") (name "Net-(Q601-B)") (class "Default")
      (node (ref "Q601") (pin "2") (pinfunction "B_2") (pintype "passive"))
      (node (ref "R601") (pin "2") (pinfunction "2_2") (pintype "passive"))
    )
    (net (code "71") (name "Net-(Q601-C)") (class "Default")
      (node (ref "Q601") (pin "1") (pinfunction "C_1") (pintype "passive"))
      (node (ref "R602") (pin "2") (pinfunction "2_2") (pintype "passive"))
      (node (ref "R603") (pin "1") (pinfunction "1_1") (pintype "passive"))
    )
    (net (code "72") (name "Net-(U$2-Pad13)") (class "Default")
      (node (ref "U$2") (pin "13") (pinfunction "13_13") (pintype "passive"))
      (node (ref "U$2") (pin "14") (pinfunction "14_14") (pintype "passive"))
    )
    (net (code "73") (name "Net-(U$2-Pad15)") (class "Default")
      (node (ref "U$2") (pin "15") (pinfunction "15_15") (pintype "passive"))
      (node (ref "U$2") (pin "16") (pinfunction "16_16") (pintype "passive"))
    )
    (net (code "74") (name "V+") (class "Default")
      (node (ref "IC3") (pin "1") (pinfunction "VDD_1") (pintype "power_in"))
      (node (ref "IC3") (pin "9") (pinfunction "#SHDN_9") (pintype "input"))
    )
    (net (code "75") (name "unconnected-(JACK7-4-PadP$1)") (class "Default")
      (node (ref "JACK7") (pin "P$1") (pinfunction "4_P$1") (pintype "passive"))
    )
    (net (code "76") (name "unconnected-(JACK8-4-PadP$1)") (class "Default")
      (node (ref "JACK8") (pin "P$1") (pinfunction "4_P$1") (pintype "passive"))
    )
    (net (code "77") (name "unconnected-(JACK9-4-PadP$1)") (class "Default")
      (node (ref "JACK9") (pin "P$1") (pinfunction "4_P$1") (pintype "passive"))
    )
    (net (code "78") (name "unconnected-(JACK10-4-PadP$1)") (class "Default")
      (node (ref "JACK10") (pin "P$1") (pinfunction "4_P$1") (pintype "passive"))
    )
    (net (code "79") (name "unconnected-(JACK10-5-PadP$3)") (class "Default")
      (node (ref "JACK10") (pin "P$3") (pinfunction "5_P$3") (pintype "passive"))
    )
  )
)
